# Sheet1.net
KiCad netlist of a schematic drawn in Altium Designer
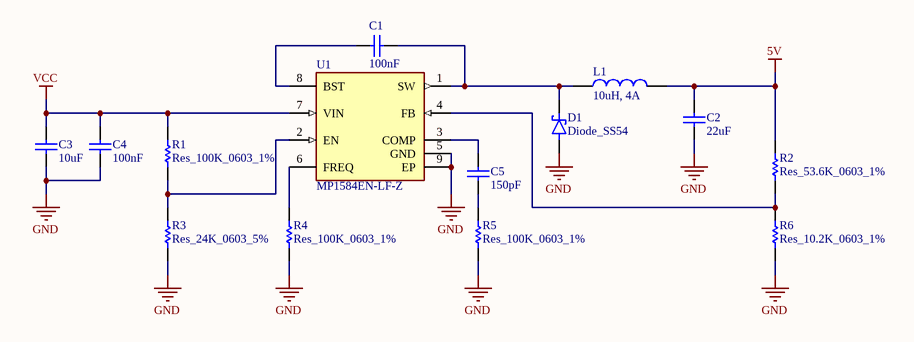
[diagram p0: Sheet1.SchDoc]

(export (version "E")
  (design (tool "Eeschema 10.0.6"))
  (components
    (comp (ref "C1")
      (value "100nF")
      (footprint "CAP_0603")
      (description "CAP, size 0603, 100nF, 50V")
      (fields (field (name "SUPPLY PART NUMBER") "Tụ Gốm 0603 100nF (0.1uF) 25V"))
      (libsource (lib "BluetoothTracking") (part "Ceramic_Cap_100nF_0603"))
    )
    (comp (ref "C2")
      (value "22uF")
      (footprint "CAP_0805")
      (description "CAP, size 0805, 22uF, 6.3V")
      (fields (field (name "SUPPLY PART NUMBER") "Tụ Gốm 0805 22uF 6.3V"))
      (libsource (lib "BluetoothTracking") (part "Ceramic_Cap_22uF_0805"))
    )
    (comp (ref "C3")
      (value "10uF")
      (footprint "CAP_0805")
      (description "CAP, size 0805, 10uF, 50V")
      (fields (field (name "SUPPLY PART NUMBER") "Tụ Gốm 0805 10uF 50V"))
      (libsource (lib "BluetoothTracking") (part "Ceramic_Cap_10uF_0805"))
    )
    (comp (ref "C4")
      (value "100nF")
      (footprint "CAP_0603")
      (description "CAP, size 0603, 100nF, 50V")
      (fields (field (name "SUPPLY PART NUMBER") "Tụ Gốm 0603 100nF (0.1uF) 25V"))
      (libsource (lib "BluetoothTracking") (part "Ceramic_Cap_100nF_0603"))
    )
    (comp (ref "C5")
      (value "150pF")
      (footprint "CAP_0603")
      (description "CAP, size 0603, 150pF, 50V")
      (fields (field (name "SUPPLY PART NUMBER") "Tụ Gốm 0603 150pF 50V"))
      (libsource (lib "BluetoothTracking") (part "Ceramic_Cap_150pF_0603"))
    )
    (comp (ref "D1")
      (value "Diode_SS54")
      (footprint "D_SMA")
      (description "Diode Schottky 40V 5A Surface Mount SMA")
      (fields (field (name "SUPPLY PART NUMBER") "SS54 SMA Diode Shotky 5A 40V"))
      (libsource (lib "BluetoothTracking") (part "Diode_SS54"))
    )
    (comp (ref "L1")
      (value "10uH, 4A")
      (footprint "Inductor_0630")
      (description "10uH, 4A, Size 0630")
      (fields (field (name "SUPPLY PART NUMBER") "Cuộn cảm 10UH 0630"))
      (libsource (lib "BluetoothTracking") (part "IND_10uH_0630"))
    )
    (comp (ref "R1")
      (value "Res_100K_0603_1%")
      (footprint "Resistor_0603")
      (description "Resistor 0603 100KOhm 1% 1_10W")
      (fields (field (name "SUPPLY PART NUMBER") "Điện Trở 100 KOhm 0603 1%"))
      (libsource (lib "BluetoothTracking") (part "Res_100K_0603_1%"))
    )
    (comp (ref "R2")
      (value "Res_53.6K_0603_1%")
      (footprint "Resistor_0603")
      (description "Resistor 0603 53.6KOhm 1% 1_10W")
      (fields (field (name "SUPPLY PART NUMBER") "Điện Trở 53.6 KOhm 0603 1%"))
      (libsource (lib "BluetoothTracking") (part "Res_53.6K_0603_1%"))
    )
    (comp (ref "R3")
      (value "Res_24K_0603_5%")
      (footprint "Resistor_0603")
      (description "Resistor 0603 24KOhm 5% 1_10W")
      (fields (field (name "SUPPLY PART NUMBER") "Điện Trở 24 KOhm 0603 5%"))
      (libsource (lib "BluetoothTracking") (part "Res_24K_0603_5%"))
    )
    (comp (ref "R4")
      (value "Res_100K_0603_1%")
      (footprint "Resistor_0603")
      (description "Resistor 0603 100KOhm 1% 1_10W")
      (fields (field (name "SUPPLY PART NUMBER") "Điện Trở 100 KOhm 0603 1%"))
      (libsource (lib "BluetoothTracking") (part "Res_100K_0603_1%"))
    )
    (comp (ref "R5")
      (value "Res_100K_0603_1%")
      (footprint "Resistor_0603")
      (description "Resistor 0603 100KOhm 1% 1_10W")
      (fields (field (name "SUPPLY PART NUMBER") "Điện Trở 100 KOhm 0603 1%"))
      (libsource (lib "BluetoothTracking") (part "Res_100K_0603_1%"))
    )
    (comp (ref "R6")
      (value "Res_10.2K_0603_1%")
      (footprint "Resistor_0603")
      (description "Resistor 0603 10.2KOhm 1% 1_10W")
      (fields (field (name "SUPPLY PART NUMBER") "Điện Trở 10.2 KOhm 0603 1%"))
      (libsource (lib "BluetoothTracking") (part "Res_10.2K_0603_1%"))
    )
    (comp (ref "U1")
      (value "MP1584EN-LF-Z")
      (footprint "SOIC-8")
      (libsource (lib "BluetoothTracking") (part "MP1584EN-LF-Z"))
    )
  )
  (nets
    (net (code "1") (name "5V") (class "Default")
      (node (ref "C2") (pin "2") (pinfunction "2_2") (pintype "passive"))
      (node (ref "L1") (pin "2") (pinfunction "2_2") (pintype "passive"))
      (node (ref "R2") (pin "2") (pinfunction "2_2") (pintype "passive"))
    )
    (net (code "2") (name "GND") (class "Default")
      (node (ref "C2") (pin "1") (pinfunction "1_1") (pintype "passive"))
      (node (ref "C3") (pin "1") (pinfunction "1_1") (pintype "passive"))
      (node (ref "C4") (pin "1") (pinfunction "1_1") (pintype "passive"))
      (node (ref "D1") (pin "2") (pinfunction "A_2") (pintype "passive"))
      (node (ref "R3") (pin "1") (pinfunction "1_1") (pintype "passive"))
      (node (ref "R4") (pin "1") (pinfunction "1_1") (pintype "passive"))
      (node (ref "R5") (pin "1") (pinfunction "1_1") (pintype "passive"))
      (node (ref "R6") (pin "1") (pinfunction "1_1") (pintype "passive"))
      (node (ref "U1") (pin "5") (pinfunction "GND_5") (pintype "power_in"))
      (node (ref "U1") (pin "9") (pinfunction "EP_9") (pintype "power_in"))
    )
    (net (code "3") (name "Net-(C5-Pad1)") (class "Default")
      (node (ref "C5") (pin "1") (pinfunction "1_1") (pintype "passive"))
      (node (ref "R5") (pin "2") (pinfunction "2_2") (pintype "passive"))
    )
    (net (code "4") (name "Net-(D1-C)") (class "Default")
      (node (ref "C1") (pin "2") (pinfunction "2_2") (pintype "passive"))
      (node (ref "D1") (pin "1") (pinfunction "C_1") (pintype "passive"))
      (node (ref "L1") (pin "1") (pinfunction "1_1") (pintype "passive"))
      (node (ref "U1") (pin "1") (pinfunction "SW_1") (pintype "output"))
    )
    (net (code "5") (name "Net-(U1-BST)") (class "Default")
      (node (ref "C1") (pin "1") (pinfunction "1_1") (pintype "passive"))
      (node (ref "U1") (pin "8") (pinfunction "BST_8") (pintype "passive"))
    )
    (net (code "6") (name "Net-(U1-COMP)") (class "Default")
      (node (ref "C5") (pin "2") (pinfunction "2_2") (pintype "passive"))
      (node (ref "U1") (pin "3") (pinfunction "COMP_3") (pintype "passive"))
    )
    (net (code "7") (name "Net-(U1-EN)") (class "Default")
      (node (ref "R1") (pin "1") (pinfunction "1_1") (pintype "passive"))
      (node (ref "R3") (pin "2") (pinfunction "2_2") (pintype "passive"))
      (node (ref "U1") (pin "2") (pinfunction "EN_2") (pintype "input"))
    )
    (net (code "8") (name "Net-(U1-FB)") (class "Default")
      (node (ref "R2") (pin "1") (pinfunction "1_1") (pintype "passive"))
      (node (ref "R6") (pin "2") (pinfunction "2_2") (pintype "passive"))
      (node (ref "U1") (pin "4") (pinfunction "FB_4") (pintype "input"))
    )
    (net (code "9") (name "Net-(U1-FREQ)") (class "Default")
      (node (ref "R4") (pin "2") (pinfunction "2_2") (pintype "passive"))
      (node (ref "U1") (pin "6") (pinfunction "FREQ_6") (pintype "passive"))
    )
    (net (code "10") (name "VCC") (class "Default")
      (node (ref "C3") (pin "2") (pinfunction "2_2") (pintype "passive"))
      (node (ref "C4") (pin "2") (pinfunction "2_2") (pintype "passive"))
      (node (ref "R1") (pin "2") (pinfunction "2_2") (pintype "passive"))
      (node (ref "U1") (pin "7") (pinfunction "VIN_7") (pintype "input"))
    )
  )
)
